# source_eagle.net
KiCad netlist of a schematic drawn in EAGLE
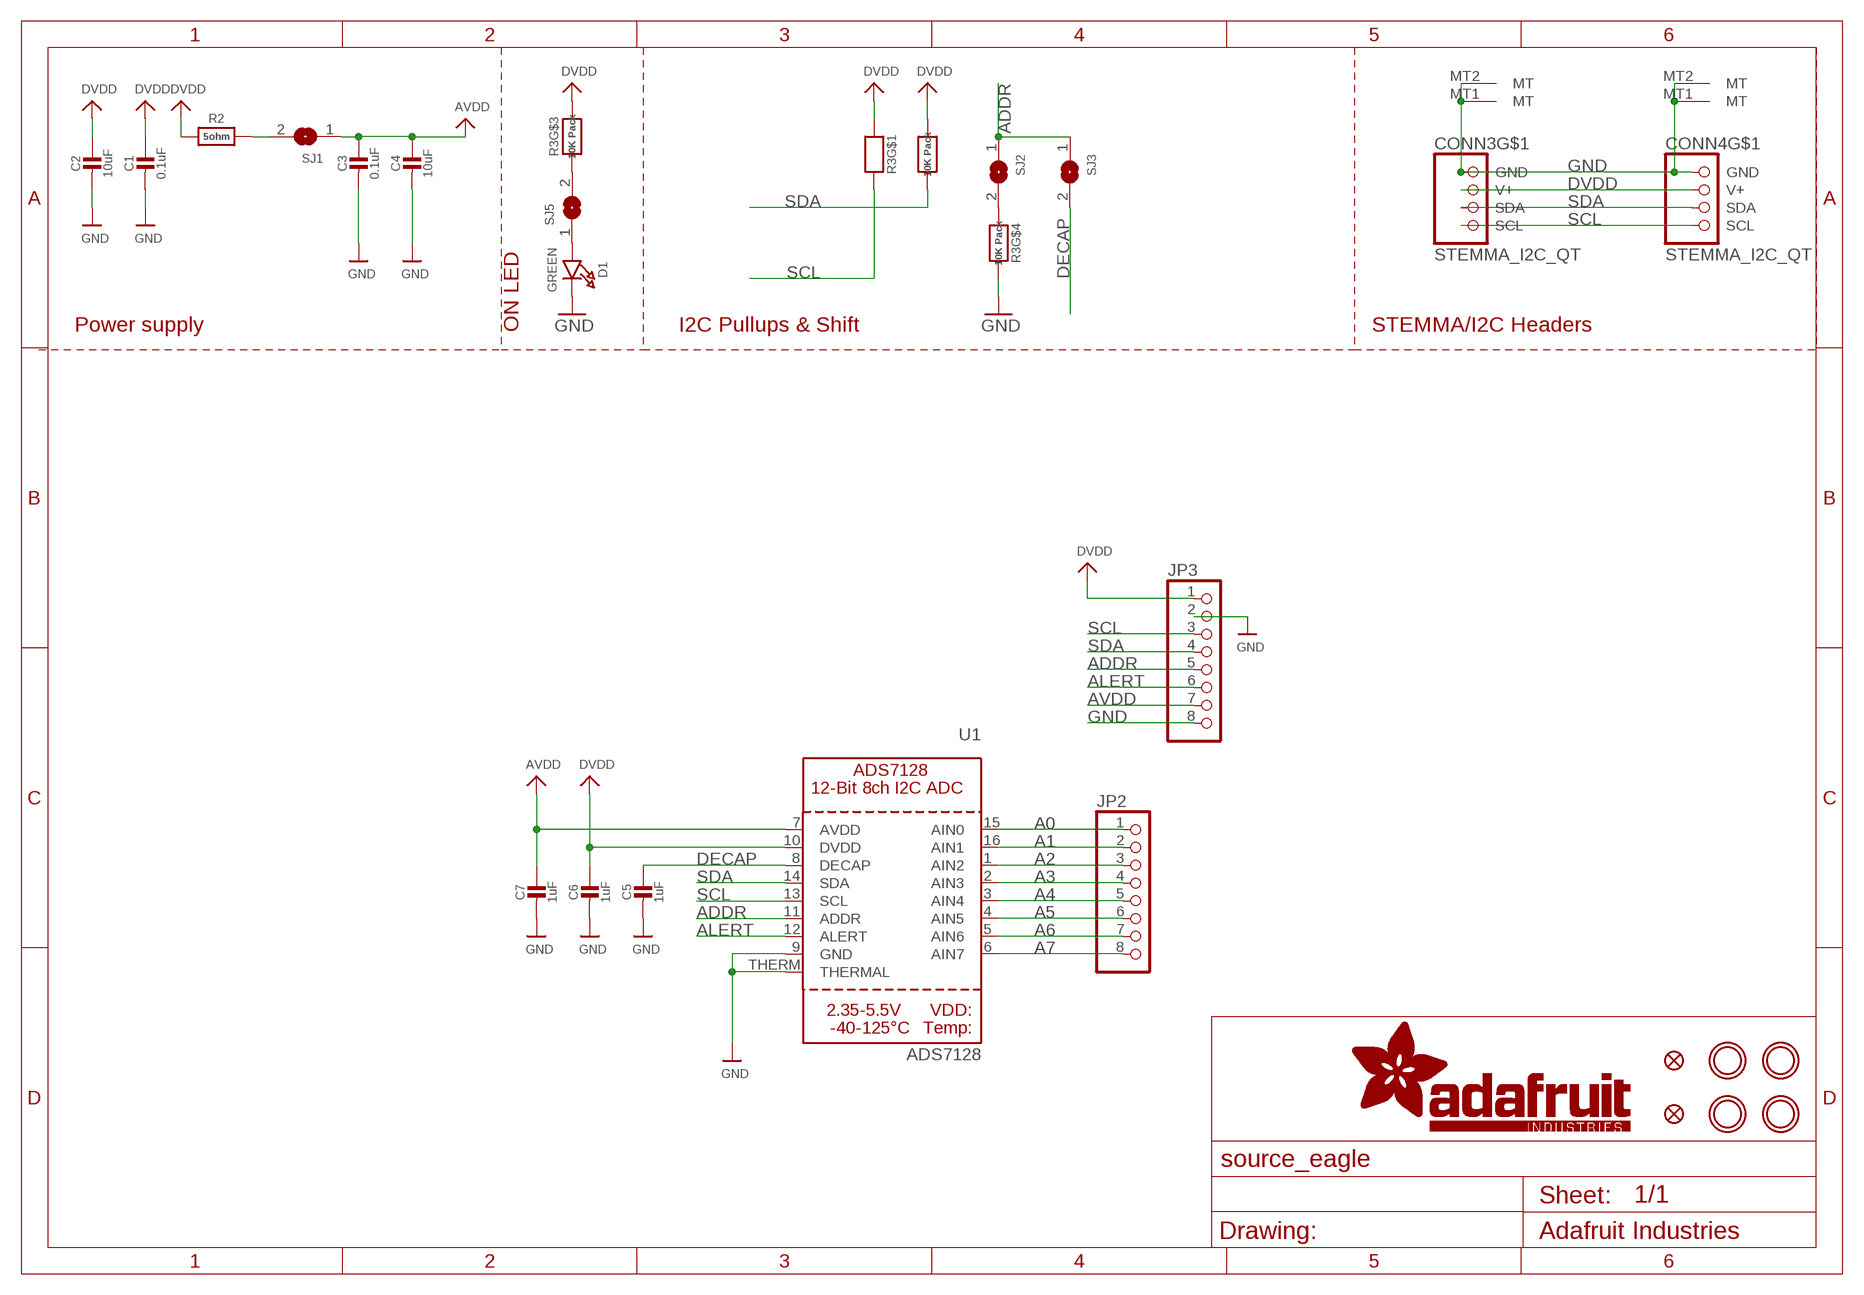
[diagram p0: schematic, sheet 1]

(export (version "E")
  (design (tool "Eeschema 10.0.6"))
  (components
    (comp (ref "C1")
      (value "0.1uF")
      (footprint "eagle-import:0603-NO")
      (libsource (lib "eagle-import") (part "CAP_CERAMIC0603_NO"))
    )
    (comp (ref "C2")
      (value "10uF")
      (footprint "eagle-import:0805-NO")
      (libsource (lib "eagle-import") (part "CAP_CERAMIC0805-NOOUTLINE"))
    )
    (comp (ref "C3")
      (value "0.1uF")
      (footprint "eagle-import:0603-NO")
      (libsource (lib "eagle-import") (part "CAP_CERAMIC0603_NO"))
    )
    (comp (ref "C4")
      (value "10uF")
      (footprint "eagle-import:0805-NO")
      (libsource (lib "eagle-import") (part "CAP_CERAMIC0805-NOOUTLINE"))
    )
    (comp (ref "C5")
      (value "1uF")
      (footprint "eagle-import:0603-NO")
      (libsource (lib "eagle-import") (part "CAP_CERAMIC0603_NO"))
    )
    (comp (ref "C6")
      (value "1uF")
      (footprint "eagle-import:0603-NO")
      (libsource (lib "eagle-import") (part "CAP_CERAMIC0603_NO"))
    )
    (comp (ref "C7")
      (value "1uF")
      (footprint "eagle-import:0603-NO")
      (libsource (lib "eagle-import") (part "CAP_CERAMIC0603_NO"))
    )
    (comp (ref "CONN3")
      (value "STEMMA_I2C_QT")
      (footprint "eagle-import:JST_SH4")
      (libsource (lib "eagle-import") (part "STEMMA_I2C_QT"))
    )
    (comp (ref "CONN4")
      (value "STEMMA_I2C_QT")
      (footprint "eagle-import:JST_SH4")
      (libsource (lib "eagle-import") (part "STEMMA_I2C_QT"))
    )
    (comp (ref "D1")
      (value "GREEN")
      (footprint "eagle-import:CHIPLED_0603_NOOUTLINE")
      (libsource (lib "eagle-import") (part "LED0603_NOOUTLINE"))
    )
    (comp (ref "FID3")
      (value "FIDUCIAL_0.5MM")
      (footprint "eagle-import:FIDUCIAL_0.5MM")
      (libsource (lib "eagle-import") (part "FIDUCIAL_0.5MM"))
    )
    (comp (ref "FID4")
      (value "FIDUCIAL_0.5MM")
      (footprint "eagle-import:FIDUCIAL_0.5MM")
      (libsource (lib "eagle-import") (part "FIDUCIAL_0.5MM"))
    )
    (comp (ref "JP2")
      (value "HEADER-1X870MIL")
      (footprint "eagle-import:1X08_ROUND_70")
      (libsource (lib "eagle-import") (part "HEADER-1X870MIL"))
    )
    (comp (ref "JP3")
      (value "HEADER-1X870MIL")
      (footprint "eagle-import:1X08_ROUND_70")
      (libsource (lib "eagle-import") (part "HEADER-1X870MIL"))
    )
    (comp (ref "R2")
      (value "5ohm")
      (footprint "eagle-import:0603-NO")
      (libsource (lib "eagle-import") (part "RESISTOR_0603_NOOUT"))
    )
    (comp (ref "R3")
      (value "10K Pack")
      (footprint "eagle-import:RESPACK_4X0603")
      (libsource (lib "eagle-import") (part "RESISTOR_4PACK"))
    )
    (comp (ref "SJ1")
      (value "SOLDERJUMPERCLOSED")
      (footprint "eagle-import:SOLDERJUMPER_CLOSEDWIRE")
      (libsource (lib "eagle-import") (part "SOLDERJUMPERCLOSED"))
    )
    (comp (ref "SJ2")
      (value "SOLDERJUMPER")
      (footprint "eagle-import:SOLDERJUMPER_ARROW_NOPASTE")
      (libsource (lib "eagle-import") (part "SOLDERJUMPER"))
    )
    (comp (ref "SJ3")
      (value "SOLDERJUMPER")
      (footprint "eagle-import:SOLDERJUMPER_ARROW_NOPASTE")
      (libsource (lib "eagle-import") (part "SOLDERJUMPER"))
    )
    (comp (ref "SJ5")
      (value "SOLDERJUMPERCLOSED")
      (footprint "eagle-import:SOLDERJUMPER_CLOSEDWIRE")
      (libsource (lib "eagle-import") (part "SOLDERJUMPERCLOSED"))
    )
    (comp (ref "U$1")
      (value "MOUNTINGHOLE2.5")
      (footprint "eagle-import:MOUNTINGHOLE_2.5_PLATED")
      (libsource (lib "eagle-import") (part "MOUNTINGHOLE2.5"))
    )
    (comp (ref "U$17")
      (value "MOUNTINGHOLE2.5")
      (footprint "eagle-import:MOUNTINGHOLE_2.5_PLATED")
      (libsource (lib "eagle-import") (part "MOUNTINGHOLE2.5"))
    )
    (comp (ref "U$19")
      (value "MOUNTINGHOLE2.5")
      (footprint "eagle-import:MOUNTINGHOLE_2.5_PLATED")
      (libsource (lib "eagle-import") (part "MOUNTINGHOLE2.5"))
    )
    (comp (ref "U$21")
      (value "MOUNTINGHOLE2.5")
      (footprint "eagle-import:MOUNTINGHOLE_2.5_PLATED")
      (libsource (lib "eagle-import") (part "MOUNTINGHOLE2.5"))
    )
    (comp (ref "U1")
      (value "ADS7128")
      (footprint "eagle-import:WQFN16")
      (fields (field (name "MF") "Texas Instruments") (field (name "MP") "ADS7128IRTER"))
      (libsource (lib "eagle-import") (part "ADC_ADS7128"))
    )
  )
  (nets
    (net (code "1") (name "/A0") (class "Default")
      (node (ref "JP2") (pin "1") (pinfunction "1_1") (pintype "passive"))
      (node (ref "U1") (pin "15") (pinfunction "AIN0_15") (pintype "bidirectional"))
    )
    (net (code "2") (name "/A1") (class "Default")
      (node (ref "JP2") (pin "2") (pinfunction "2_2") (pintype "passive"))
      (node (ref "U1") (pin "16") (pinfunction "AIN1_16") (pintype "bidirectional"))
    )
    (net (code "3") (name "/A2") (class "Default")
      (node (ref "JP2") (pin "3") (pinfunction "3_3") (pintype "passive"))
      (node (ref "U1") (pin "1") (pinfunction "AIN2_1") (pintype "bidirectional"))
    )
    (net (code "4") (name "/A3") (class "Default")
      (node (ref "JP2") (pin "4") (pinfunction "4_4") (pintype "passive"))
      (node (ref "U1") (pin "2") (pinfunction "AIN3_2") (pintype "bidirectional"))
    )
    (net (code "5") (name "/A4") (class "Default")
      (node (ref "JP2") (pin "5") (pinfunction "5_5") (pintype "passive"))
      (node (ref "U1") (pin "3") (pinfunction "AIN4_3") (pintype "bidirectional"))
    )
    (net (code "6") (name "/A5") (class "Default")
      (node (ref "JP2") (pin "6") (pinfunction "6_6") (pintype "passive"))
      (node (ref "U1") (pin "4") (pinfunction "AIN5_4") (pintype "bidirectional"))
    )
    (net (code "7") (name "/A6") (class "Default")
      (node (ref "JP2") (pin "7") (pinfunction "7_7") (pintype "passive"))
      (node (ref "U1") (pin "5") (pinfunction "AIN6_5") (pintype "bidirectional"))
    )
    (net (code "8") (name "/A7") (class "Default")
      (node (ref "JP2") (pin "8") (pinfunction "8_8") (pintype "passive"))
      (node (ref "U1") (pin "6") (pinfunction "AIN7_6") (pintype "bidirectional"))
    )
    (net (code "9") (name "/ADDR") (class "Default")
      (node (ref "JP3") (pin "5") (pinfunction "5_5") (pintype "passive"))
      (node (ref "SJ2") (pin "1") (pinfunction "1_1") (pintype "passive"))
      (node (ref "SJ3") (pin "1") (pinfunction "1_1") (pintype "passive"))
      (node (ref "U1") (pin "11") (pinfunction "ADDR_11") (pintype "input"))
    )
    (net (code "10") (name "/ALERT") (class "Default")
      (node (ref "JP3") (pin "6") (pinfunction "6_6") (pintype "passive"))
      (node (ref "U1") (pin "12") (pinfunction "ALERT_12") (pintype "output"))
    )
    (net (code "11") (name "/DECAP") (class "Default")
      (node (ref "C5") (pin "1") (pinfunction "1_1") (pintype "passive"))
      (node (ref "SJ3") (pin "2") (pinfunction "2_2") (pintype "passive"))
      (node (ref "U1") (pin "8") (pinfunction "DECAP_8") (pintype "power_in"))
    )
    (net (code "12") (name "/SCL") (class "Default")
      (node (ref "CONN3") (pin "4") (pinfunction "SCL_4") (pintype "passive"))
      (node (ref "CONN4") (pin "4") (pinfunction "SCL_4") (pintype "passive"))
      (node (ref "JP3") (pin "3") (pinfunction "3_3") (pintype "passive"))
      (node (ref "R3") (pin "8") (pinfunction "2_8") (pintype "passive"))
      (node (ref "U1") (pin "13") (pinfunction "SCL_13") (pintype "input"))
    )
    (net (code "13") (name "/SDA") (class "Default")
      (node (ref "CONN3") (pin "3") (pinfunction "SDA_3") (pintype "passive"))
      (node (ref "CONN4") (pin "3") (pinfunction "SDA_3") (pintype "passive"))
      (node (ref "JP3") (pin "4") (pinfunction "4_4") (pintype "passive"))
      (node (ref "R3") (pin "7") (pinfunction "2_7") (pintype "passive"))
      (node (ref "U1") (pin "14") (pinfunction "SDA_14") (pintype "bidirectional"))
    )
    (net (code "14") (name "AVDD") (class "Default")
      (node (ref "C3") (pin "1") (pinfunction "1_1") (pintype "passive"))
      (node (ref "C4") (pin "1") (pinfunction "1_1") (pintype "passive"))
      (node (ref "C7") (pin "1") (pinfunction "1_1") (pintype "passive"))
      (node (ref "JP3") (pin "7") (pinfunction "7_7") (pintype "passive"))
      (node (ref "SJ1") (pin "1") (pinfunction "1_1") (pintype "passive"))
      (node (ref "U1") (pin "7") (pinfunction "AVDD_7") (pintype "power_in"))
    )
    (net (code "15") (name "DVDD") (class "Default")
      (node (ref "C1") (pin "1") (pinfunction "1_1") (pintype "passive"))
      (node (ref "C2") (pin "1") (pinfunction "1_1") (pintype "passive"))
      (node (ref "C6") (pin "1") (pinfunction "1_1") (pintype "passive"))
      (node (ref "CONN3") (pin "2") (pinfunction "V+_2") (pintype "passive"))
      (node (ref "CONN4") (pin "2") (pinfunction "V+_2") (pintype "passive"))
      (node (ref "JP3") (pin "1") (pinfunction "1_1") (pintype "passive"))
      (node (ref "R2") (pin "1") (pinfunction "1_1") (pintype "passive"))
      (node (ref "R3") (pin "1") (pinfunction "1_1") (pintype "passive"))
      (node (ref "R3") (pin "2") (pinfunction "1_2") (pintype "passive"))
      (node (ref "R3") (pin "6") (pinfunction "2_6") (pintype "passive"))
      (node (ref "U1") (pin "10") (pinfunction "DVDD_10") (pintype "power_in"))
    )
    (net (code "16") (name "GND") (class "Default")
      (node (ref "C1") (pin "2") (pinfunction "2_2") (pintype "passive"))
      (node (ref "C2") (pin "2") (pinfunction "2_2") (pintype "passive"))
      (node (ref "C3") (pin "2") (pinfunction "2_2") (pintype "passive"))
      (node (ref "C4") (pin "2") (pinfunction "2_2") (pintype "passive"))
      (node (ref "C5") (pin "2") (pinfunction "2_2") (pintype "passive"))
      (node (ref "C6") (pin "2") (pinfunction "2_2") (pintype "passive"))
      (node (ref "C7") (pin "2") (pinfunction "2_2") (pintype "passive"))
      (node (ref "CONN3") (pin "1") (pinfunction "GND_1") (pintype "passive"))
      (node (ref "CONN3") (pin "MT1") (pinfunction "MT_MT1") (pintype "bidirectional"))
      (node (ref "CONN3") (pin "MT2") (pinfunction "MT_MT2") (pintype "bidirectional"))
      (node (ref "CONN4") (pin "1") (pinfunction "GND_1") (pintype "passive"))
      (node (ref "CONN4") (pin "MT1") (pinfunction "MT_MT1") (pintype "bidirectional"))
      (node (ref "CONN4") (pin "MT2") (pinfunction "MT_MT2") (pintype "bidirectional"))
      (node (ref "D1") (pin "C") (pinfunction "C_C") (pintype "passive"))
      (node (ref "JP3") (pin "2") (pinfunction "2_2") (pintype "passive"))
      (node (ref "JP3") (pin "8") (pinfunction "8_8") (pintype "passive"))
      (node (ref "R3") (pin "5") (pinfunction "2_5") (pintype "passive"))
      (node (ref "U1") (pin "9") (pinfunction "GND_9") (pintype "power_in"))
      (node (ref "U1") (pin "THERM") (pinfunction "THERMAL_THERM") (pintype "power_in"))
    )
    (net (code "17") (name "Net-(D1-PadA)") (class "Default")
      (node (ref "D1") (pin "A") (pinfunction "A_A") (pintype "passive"))
      (node (ref "SJ5") (pin "1") (pinfunction "1_1") (pintype "passive"))
    )
    (net (code "18") (name "Net-(R2-Pad2)") (class "Default")
      (node (ref "R2") (pin "2") (pinfunction "2_2") (pintype "passive"))
      (node (ref "SJ1") (pin "2") (pinfunction "2_2") (pintype "passive"))
    )
    (net (code "19") (name "Net-(R3C-1)") (class "Default")
      (node (ref "R3") (pin "3") (pinfunction "1_3") (pintype "passive"))
      (node (ref "SJ5") (pin "2") (pinfunction "2_2") (pintype "passive"))
    )
    (net (code "20") (name "Net-(R3D-1)") (class "Default")
      (node (ref "R3") (pin "4") (pinfunction "1_4") (pintype "passive"))
      (node (ref "SJ2") (pin "2") (pinfunction "2_2") (pintype "passive"))
    )
  )
)
